# attiny85.net
KiCad netlist of a schematic drawn in EAGLE
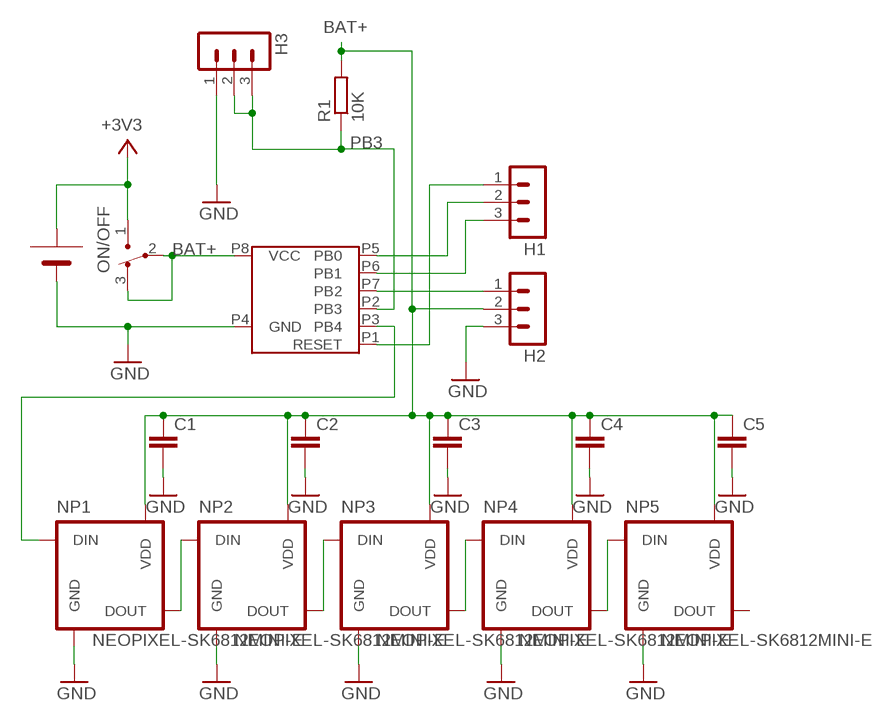
[diagram p0: schematic, sheet 1]

(export (version "E")
  (design (tool "Eeschema 10.0.6"))
  (components
    (comp (ref "ATTINY85-1")
      (value "ATTINY85")
      (footprint "eagle-import:ATTINY85-20SUR")
      (libsource (lib "eagle-import") (part "ATTINY85SOP8"))
    )
    (comp (ref "BAT1")
      (value "BAT-CR2032C")
      (footprint "eagle-import:BAT-CR2032-3")
      (libsource (lib "eagle-import") (part "BAT-CR2032C"))
    )
    (comp (ref "C1")
      (value "C-EUC2012")
      (footprint "eagle-import:C2012")
      (libsource (lib "eagle-import") (part "C-EUC2012"))
    )
    (comp (ref "C2")
      (value "C-EUC2012")
      (footprint "eagle-import:C2012")
      (libsource (lib "eagle-import") (part "C-EUC2012"))
    )
    (comp (ref "C3")
      (value "C-EUC2012")
      (footprint "eagle-import:C2012")
      (libsource (lib "eagle-import") (part "C-EUC2012"))
    )
    (comp (ref "C4")
      (value "C-EUC2012")
      (footprint "eagle-import:C2012")
      (libsource (lib "eagle-import") (part "C-EUC2012"))
    )
    (comp (ref "C5")
      (value "C-EUC2012")
      (footprint "eagle-import:C2012")
      (libsource (lib "eagle-import") (part "C-EUC2012"))
    )
    (comp (ref "H1")
      (value "PINHEAD-MA03-1SMD")
      (footprint "eagle-import:PINHEAD-MA03-2")
      (libsource (lib "eagle-import") (part "PINHEAD-MA03-1SMD"))
    )
    (comp (ref "H2")
      (value "PINHEAD-MA03-1SMD")
      (footprint "eagle-import:PINHEAD-MA03-2")
      (libsource (lib "eagle-import") (part "PINHEAD-MA03-1SMD"))
    )
    (comp (ref "H3")
      (value "PINHEAD-MA03-1")
      (footprint "eagle-import:PINHEAD-MA03-1")
      (libsource (lib "eagle-import") (part "PINHEAD-MA03-1"))
    )
    (comp (ref "NP1")
      (value "NEOPIXEL-SK6812MINI-E")
      (footprint "eagle-import:SK6812MINI-E")
      (libsource (lib "eagle-import") (part "NEOPIXEL-SK6812MINI-E"))
    )
    (comp (ref "NP2")
      (value "NEOPIXEL-SK6812MINI-E")
      (footprint "eagle-import:SK6812MINI-E")
      (libsource (lib "eagle-import") (part "NEOPIXEL-SK6812MINI-E"))
    )
    (comp (ref "NP3")
      (value "NEOPIXEL-SK6812MINI-E")
      (footprint "eagle-import:SK6812MINI-E")
      (libsource (lib "eagle-import") (part "NEOPIXEL-SK6812MINI-E"))
    )
    (comp (ref "NP4")
      (value "NEOPIXEL-SK6812MINI-E")
      (footprint "eagle-import:SK6812MINI-E")
      (libsource (lib "eagle-import") (part "NEOPIXEL-SK6812MINI-E"))
    )
    (comp (ref "NP5")
      (value "NEOPIXEL-SK6812MINI-E")
      (footprint "eagle-import:SK6812MINI-E")
      (libsource (lib "eagle-import") (part "NEOPIXEL-SK6812MINI-E"))
    )
    (comp (ref "ON/OFF")
      (value "POWER")
      (footprint "eagle-import:SW3-1")
      (fields (field (name "MF") "HiLetgo"))
      (libsource (lib "eagle-import") (part "SW3-1"))
    )
    (comp (ref "R1")
      (value "10K")
      (footprint "eagle-import:M3216")
      (libsource (lib "eagle-import") (part "R-EU_M3216"))
    )
  )
  (nets
    (net (code "1") (name "+3V3") (class "Default")
      (node (ref "BAT1") (pin "V+") (pinfunction "BAT+_V+") (pintype "bidirectional"))
      (node (ref "ON/OFF") (pin "1") (pinfunction "1_1") (pintype "passive"))
    )
    (net (code "2") (name "/BAT+") (class "Default")
      (node (ref "ATTINY85-1") (pin "P8") (pinfunction "VCC_P8") (pintype "bidirectional"))
      (node (ref "C1") (pin "1") (pinfunction "1_1") (pintype "passive"))
      (node (ref "C2") (pin "1") (pinfunction "1_1") (pintype "passive"))
      (node (ref "C3") (pin "1") (pinfunction "1_1") (pintype "passive"))
      (node (ref "C4") (pin "1") (pinfunction "1_1") (pintype "passive"))
      (node (ref "C5") (pin "1") (pinfunction "1_1") (pintype "passive"))
      (node (ref "H2") (pin "2") (pinfunction "2_2") (pintype "passive"))
      (node (ref "NP1") (pin "VDD") (pinfunction "VDD_VDD") (pintype "bidirectional"))
      (node (ref "NP2") (pin "VDD") (pinfunction "VDD_VDD") (pintype "bidirectional"))
      (node (ref "NP3") (pin "VDD") (pinfunction "VDD_VDD") (pintype "bidirectional"))
      (node (ref "NP4") (pin "VDD") (pinfunction "VDD_VDD") (pintype "bidirectional"))
      (node (ref "NP5") (pin "VDD") (pinfunction "VDD_VDD") (pintype "bidirectional"))
      (node (ref "ON/OFF") (pin "2") (pinfunction "2_2") (pintype "passive"))
      (node (ref "ON/OFF") (pin "3") (pinfunction "3_3") (pintype "passive"))
      (node (ref "R1") (pin "2") (pinfunction "2_2") (pintype "passive"))
    )
    (net (code "3") (name "/PB3") (class "Default")
      (node (ref "ATTINY85-1") (pin "P2") (pinfunction "PB3_P2") (pintype "bidirectional"))
      (node (ref "H3") (pin "2") (pinfunction "2_2") (pintype "passive"))
      (node (ref "H3") (pin "3") (pinfunction "3_3") (pintype "passive"))
      (node (ref "R1") (pin "1") (pinfunction "1_1") (pintype "passive"))
    )
    (net (code "4") (name "GND") (class "Default")
      (node (ref "ATTINY85-1") (pin "P4") (pinfunction "GND_P4") (pintype "bidirectional"))
      (node (ref "BAT1") (pin "V-") (pinfunction "P$1_V-") (pintype "bidirectional"))
      (node (ref "C1") (pin "2") (pinfunction "2_2") (pintype "passive"))
      (node (ref "C2") (pin "2") (pinfunction "2_2") (pintype "passive"))
      (node (ref "C3") (pin "2") (pinfunction "2_2") (pintype "passive"))
      (node (ref "C4") (pin "2") (pinfunction "2_2") (pintype "passive"))
      (node (ref "C5") (pin "2") (pinfunction "2_2") (pintype "passive"))
      (node (ref "H2") (pin "3") (pinfunction "3_3") (pintype "passive"))
      (node (ref "H3") (pin "1") (pinfunction "1_1") (pintype "passive"))
      (node (ref "NP1") (pin "GND") (pinfunction "GND_GND") (pintype "bidirectional"))
      (node (ref "NP2") (pin "GND") (pinfunction "GND_GND") (pintype "bidirectional"))
      (node (ref "NP3") (pin "GND") (pinfunction "GND_GND") (pintype "bidirectional"))
      (node (ref "NP4") (pin "GND") (pinfunction "GND_GND") (pintype "bidirectional"))
      (node (ref "NP5") (pin "GND") (pinfunction "GND_GND") (pintype "bidirectional"))
    )
    (net (code "5") (name "Net-(ATTINY85-1-PB0)") (class "Default")
      (node (ref "ATTINY85-1") (pin "P5") (pinfunction "PB0_P5") (pintype "bidirectional"))
      (node (ref "H1") (pin "2") (pinfunction "2_2") (pintype "passive"))
    )
    (net (code "6") (name "Net-(ATTINY85-1-PB1)") (class "Default")
      (node (ref "ATTINY85-1") (pin "P6") (pinfunction "PB1_P6") (pintype "bidirectional"))
      (node (ref "H1") (pin "3") (pinfunction "3_3") (pintype "passive"))
    )
    (net (code "7") (name "Net-(ATTINY85-1-PB2)") (class "Default")
      (node (ref "ATTINY85-1") (pin "P7") (pinfunction "PB2_P7") (pintype "bidirectional"))
      (node (ref "H2") (pin "1") (pinfunction "1_1") (pintype "passive"))
    )
    (net (code "8") (name "Net-(ATTINY85-1-PB4)") (class "Default")
      (node (ref "ATTINY85-1") (pin "P3") (pinfunction "PB4_P3") (pintype "bidirectional"))
      (node (ref "NP1") (pin "DIN") (pinfunction "DIN_DIN") (pintype "input"))
    )
    (net (code "9") (name "Net-(ATTINY85-1-RESET)") (class "Default")
      (node (ref "ATTINY85-1") (pin "P1") (pinfunction "RESET_P1") (pintype "bidirectional"))
      (node (ref "H1") (pin "1") (pinfunction "1_1") (pintype "passive"))
    )
    (net (code "10") (name "Net-(NP1-PadDOUT)") (class "Default")
      (node (ref "NP1") (pin "DOUT") (pinfunction "DOUT_DOUT") (pintype "output"))
      (node (ref "NP2") (pin "DIN") (pinfunction "DIN_DIN") (pintype "input"))
    )
    (net (code "11") (name "Net-(NP2-PadDOUT)") (class "Default")
      (node (ref "NP2") (pin "DOUT") (pinfunction "DOUT_DOUT") (pintype "output"))
      (node (ref "NP3") (pin "DIN") (pinfunction "DIN_DIN") (pintype "input"))
    )
    (net (code "12") (name "Net-(NP3-PadDOUT)") (class "Default")
      (node (ref "NP3") (pin "DOUT") (pinfunction "DOUT_DOUT") (pintype "output"))
      (node (ref "NP4") (pin "DIN") (pinfunction "DIN_DIN") (pintype "input"))
    )
    (net (code "13") (name "Net-(NP4-PadDOUT)") (class "Default")
      (node (ref "NP4") (pin "DOUT") (pinfunction "DOUT_DOUT") (pintype "output"))
      (node (ref "NP5") (pin "DIN") (pinfunction "DIN_DIN") (pintype "input"))
    )
    (net (code "14") (name "unconnected-(NP5-PadDOUT)") (class "Default")
      (node (ref "NP5") (pin "DOUT") (pinfunction "DOUT_DOUT") (pintype "output"))
    )
  )
)
